# PCIE_CLK.net
KiCad netlist of a schematic drawn in Altium Designer
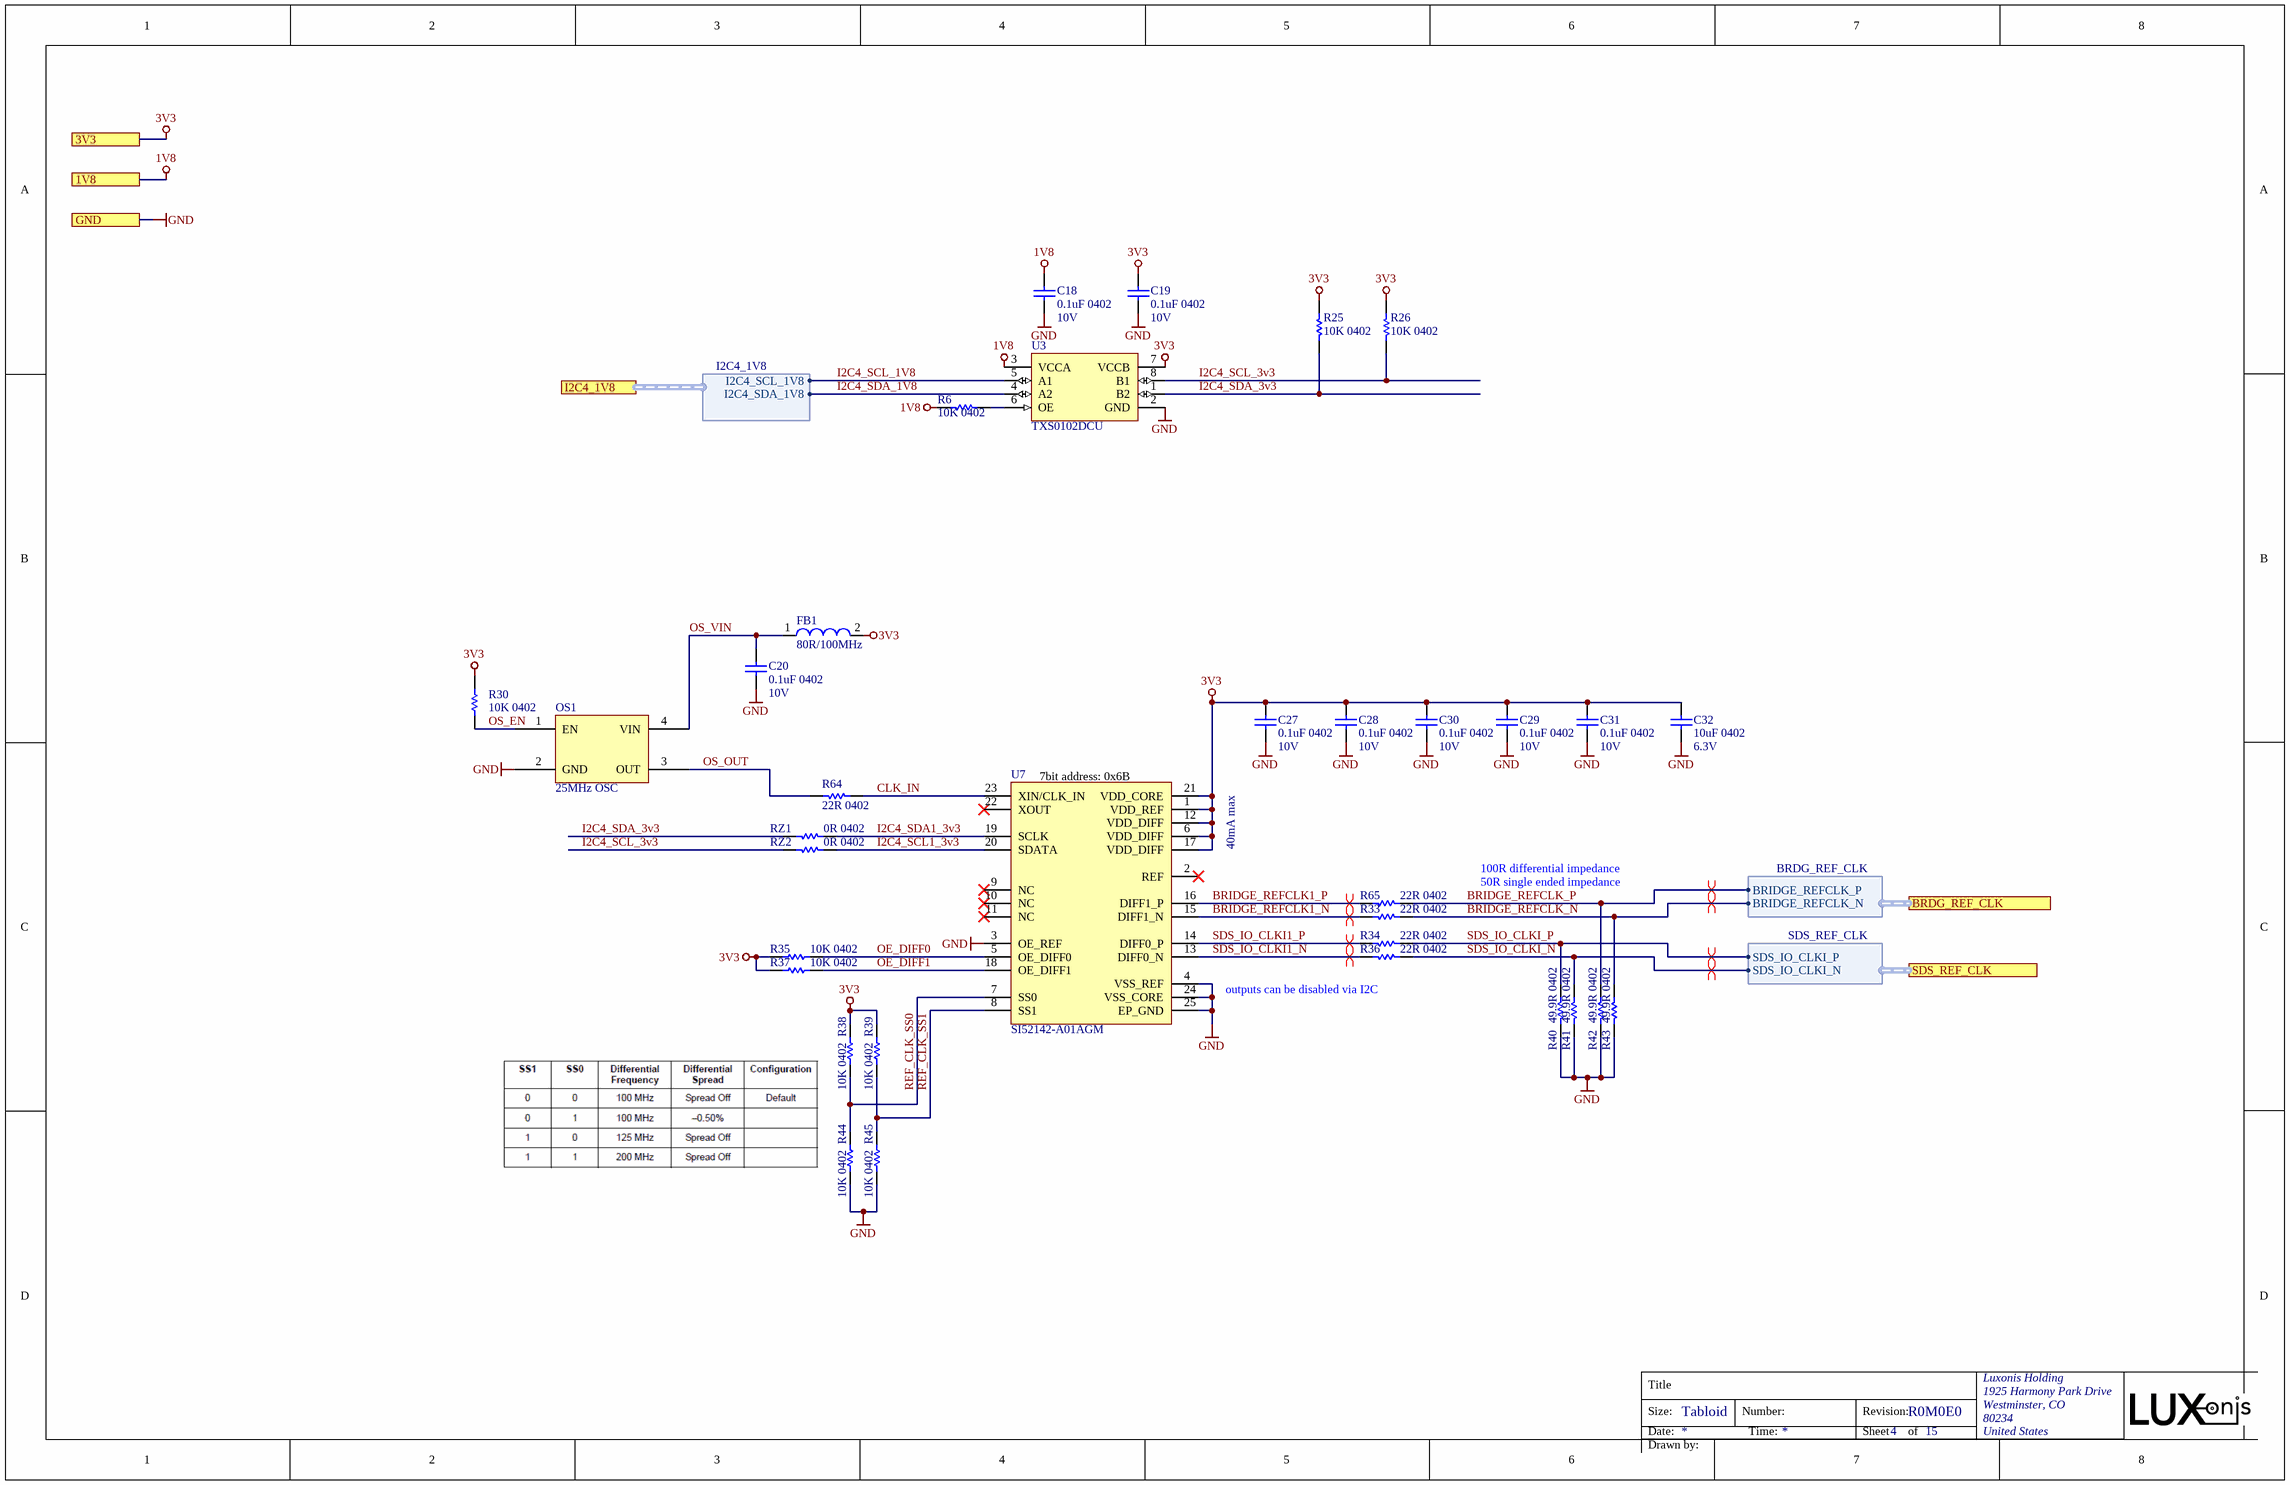
[diagram p0: PCIE_CLK.SchDoc]

(export (version "E")
  (design (tool "Eeschema 10.0.6"))
  (components
    (comp (ref "C18")
      (value "0.1uF 0402")
      (footprint "CAP_Altium_Vault_Generic:CAPC0402(1005)70_N")
      (description "CAP CER 0.1UF 10V X7R 0402 5%")
      (fields (field (name "TOLERANCE") "5%") (field (name "VOLTAGE RATING") "10V"))
      (libsource (lib "LuxonisMaster") (part "GRM155R71A104JA01D"))
    )
    (comp (ref "C19")
      (value "0.1uF 0402")
      (footprint "CAP_Altium_Vault_Generic:CAPC0402(1005)70_N")
      (description "CAP CER 0.1UF 10V X7R 0402 5%")
      (fields (field (name "TOLERANCE") "5%") (field (name "VOLTAGE RATING") "10V"))
      (libsource (lib "LuxonisMaster") (part "GRM155R71A104JA01D"))
    )
    (comp (ref "C20")
      (value "0.1uF 0402")
      (footprint "CAP_Altium_Vault_Generic:CAPC0402(1005)70_N")
      (description "CAP CER 0.1UF 10V X7R 0402 5%")
      (fields (field (name "TOLERANCE") "5%") (field (name "VOLTAGE RATING") "10V"))
      (libsource (lib "LuxonisMaster") (part "GRM155R71A104JA01D"))
    )
    (comp (ref "C27")
      (value "0.1uF 0402")
      (footprint "CAP_Altium_Vault_Generic:CAPC0402(1005)70_N")
      (description "CAP CER 0.1UF 10V X7R 0402 5%")
      (fields (field (name "TOLERANCE") "5%") (field (name "VOLTAGE RATING") "10V"))
      (libsource (lib "LuxonisMaster") (part "GRM155R71A104JA01D"))
    )
    (comp (ref "C28")
      (value "0.1uF 0402")
      (footprint "CAP_Altium_Vault_Generic:CAPC0402(1005)70_N")
      (description "CAP CER 0.1UF 10V X7R 0402 5%")
      (fields (field (name "TOLERANCE") "5%") (field (name "VOLTAGE RATING") "10V"))
      (libsource (lib "LuxonisMaster") (part "GRM155R71A104JA01D"))
    )
    (comp (ref "C29")
      (value "0.1uF 0402")
      (footprint "CAP_Altium_Vault_Generic:CAPC0402(1005)70_N")
      (description "CAP CER 0.1UF 10V X7R 0402 5%")
      (fields (field (name "TOLERANCE") "5%") (field (name "VOLTAGE RATING") "10V"))
      (libsource (lib "LuxonisMaster") (part "GRM155R71A104JA01D"))
    )
    (comp (ref "C30")
      (value "0.1uF 0402")
      (footprint "CAP_Altium_Vault_Generic:CAPC0402(1005)70_N")
      (description "CAP CER 0.1UF 10V X7R 0402 5%")
      (fields (field (name "TOLERANCE") "5%") (field (name "VOLTAGE RATING") "10V"))
      (libsource (lib "LuxonisMaster") (part "GRM155R71A104JA01D"))
    )
    (comp (ref "C31")
      (value "0.1uF 0402")
      (footprint "CAP_Altium_Vault_Generic:CAPC0402(1005)70_N")
      (description "CAP CER 0.1UF 10V X7R 0402 5%")
      (fields (field (name "TOLERANCE") "5%") (field (name "VOLTAGE RATING") "10V"))
      (libsource (lib "LuxonisMaster") (part "GRM155R71A104JA01D"))
    )
    (comp (ref "C32")
      (value "10uF 0402")
      (footprint "CAP_Altium_Vault_Generic:CAPC0402(1005)70_N")
      (description "CAP CER 10UF 6.3V X5R 0402 20%")
      (fields (field (name "TOLERANCE") "20%") (field (name "VOLTAGE RATING") "6.3V"))
      (libsource (lib "LuxonisMaster") (part "GRM155R60J106ME15D"))
    )
    (comp (ref "FB1")
      (value "80R/100MHz")
      (footprint "LuxonisMaster:BK1608HS800-T_N")
      (description "FERRITE BEAD 80 OHM 0603 1LN")
      (fields (field (name "TOLERANCE") "25%"))
      (libsource (lib "LuxonisMaster") (part "BK1608HS800-T"))
    )
    (comp (ref "OS1")
      (value "25MHz OSC")
      (footprint "BW2098POE:ASDMB-25.000MHZ-LC-T")
      (description "MEMS OSC XO 25.0000MHZ LVCMOS")
      (libsource (lib "BW2098POE") (part "ASDMB-25.000MHZ-LC-T"))
    )
    (comp (ref "R6")
      (value "10K 0402")
      (footprint "RESC0402(1005)_N")
      (fields (field (name "TOLERANCE") "1%"))
      (libsource (lib "LuxonisMaster") (part "RC0402FR-1310KL"))
    )
    (comp (ref "R25")
      (value "10K 0402")
      (footprint "RESC0402(1005)_N")
      (fields (field (name "TOLERANCE") "1%"))
      (libsource (lib "LuxonisMaster") (part "RC0402FR-1310KL"))
    )
    (comp (ref "R26")
      (value "10K 0402")
      (footprint "RESC0402(1005)_N")
      (fields (field (name "TOLERANCE") "1%"))
      (libsource (lib "LuxonisMaster") (part "RC0402FR-1310KL"))
    )
    (comp (ref "R30")
      (value "10K 0402")
      (footprint "RESC0402(1005)_N")
      (fields (field (name "TOLERANCE") "1%"))
      (libsource (lib "LuxonisMaster") (part "RC0402FR-1310KL"))
    )
    (comp (ref "R33")
      (value "22R 0402")
      (footprint "RES_Altium_Vault_Generic:RESC0402(1005)_L")
      (description "RES SMD 22 OHM 1% 1/16W 0402")
      (fields (field (name "TOLERANCE") "1%"))
      (libsource (lib "BW2098POE") (part "RC0402FR-0722RL"))
    )
    (comp (ref "R34")
      (value "22R 0402")
      (footprint "RES_Altium_Vault_Generic:RESC0402(1005)_L")
      (description "RES SMD 22 OHM 1% 1/16W 0402")
      (fields (field (name "TOLERANCE") "1%"))
      (libsource (lib "BW2098POE") (part "RC0402FR-0722RL"))
    )
    (comp (ref "R35")
      (value "10K 0402")
      (footprint "RESC0402(1005)_N")
      (fields (field (name "TOLERANCE") "1%"))
      (libsource (lib "LuxonisMaster") (part "RC0402FR-1310KL"))
    )
    (comp (ref "R36")
      (value "22R 0402")
      (footprint "RES_Altium_Vault_Generic:RESC0402(1005)_L")
      (description "RES SMD 22 OHM 1% 1/16W 0402")
      (fields (field (name "TOLERANCE") "1%"))
      (libsource (lib "BW2098POE") (part "RC0402FR-0722RL"))
    )
    (comp (ref "R37")
      (value "10K 0402")
      (footprint "RESC0402(1005)_N")
      (fields (field (name "TOLERANCE") "1%"))
      (libsource (lib "LuxonisMaster") (part "RC0402FR-1310KL"))
    )
    (comp (ref "R38")
      (value "10K 0402")
      (footprint "RESC0402(1005)_N")
      (fields (field (name "TOLERANCE") "1%"))
      (libsource (lib "LuxonisMaster") (part "RC0402FR-1310KL"))
    )
    (comp (ref "R39")
      (value "10K 0402")
      (footprint "RESC0402(1005)_N")
      (fields (field (name "TOLERANCE") "1%"))
      (libsource (lib "LuxonisMaster") (part "RC0402FR-1310KL"))
    )
    (comp (ref "R40")
      (value "49.9R 0402")
      (footprint "RES_Altium_Vault_Generic:RESC0402(1005)_L")
      (description "RES SMD 49.9 OHM 1% 1/16W 0402")
      (fields (field (name "TOLERANCE") "1%"))
      (libsource (lib "LuxonisMaster") (part "RC0402FR-0749R9L"))
    )
    (comp (ref "R41")
      (value "49.9R 0402")
      (footprint "RES_Altium_Vault_Generic:RESC0402(1005)_L")
      (description "RES SMD 49.9 OHM 1% 1/16W 0402")
      (fields (field (name "TOLERANCE") "1%"))
      (libsource (lib "LuxonisMaster") (part "RC0402FR-0749R9L"))
    )
    (comp (ref "R42")
      (value "49.9R 0402")
      (footprint "RES_Altium_Vault_Generic:RESC0402(1005)_L")
      (description "RES SMD 49.9 OHM 1% 1/16W 0402")
      (fields (field (name "TOLERANCE") "1%"))
      (libsource (lib "LuxonisMaster") (part "RC0402FR-0749R9L"))
    )
    (comp (ref "R43")
      (value "49.9R 0402")
      (footprint "RES_Altium_Vault_Generic:RESC0402(1005)_L")
      (description "RES SMD 49.9 OHM 1% 1/16W 0402")
      (fields (field (name "TOLERANCE") "1%"))
      (libsource (lib "LuxonisMaster") (part "RC0402FR-0749R9L"))
    )
    (comp (ref "R44")
      (value "10K 0402")
      (footprint "RESC0402(1005)_N")
      (fields (field (name "TOLERANCE") "1%"))
      (libsource (lib "LuxonisMaster") (part "RC0402FR-1310KL"))
    )
    (comp (ref "R45")
      (value "10K 0402")
      (footprint "RESC0402(1005)_N")
      (fields (field (name "TOLERANCE") "1%"))
      (libsource (lib "LuxonisMaster") (part "RC0402FR-1310KL"))
    )
    (comp (ref "R64")
      (value "22R 0402")
      (footprint "RESC0402(1005)_N")
      (description "RES SMD 22 OHM 1% 1/16W 0402")
      (fields (field (name "TOLERANCE") "1%"))
      (libsource (lib "BW2098POE") (part "RC0402FR-0722RL"))
    )
    (comp (ref "R65")
      (value "22R 0402")
      (footprint "RES_Altium_Vault_Generic:RESC0402(1005)_L")
      (description "RES SMD 22 OHM 1% 1/16W 0402")
      (fields (field (name "TOLERANCE") "1%"))
      (libsource (lib "BW2098POE") (part "RC0402FR-0722RL"))
    )
    (comp (ref "RZ1")
      (value "0R 0402")
      (footprint "RESC0402(1005)_N")
      (description "RES SMD 0 OHM JUMPER 1/16W 0402")
      (fields (field (name "TOLERANCE") "5%"))
      (libsource (lib "LuxonisMaster") (part "CRCW04020000Z0ED"))
    )
    (comp (ref "RZ2")
      (value "0R 0402")
      (footprint "RESC0402(1005)_N")
      (description "RES SMD 0 OHM JUMPER 1/16W 0402")
      (fields (field (name "TOLERANCE") "5%"))
      (libsource (lib "LuxonisMaster") (part "CRCW04020000Z0ED"))
    )
    (comp (ref "U3")
      (value "TXS0102DCU")
      (footprint "BW2098POE:TXS0102DCUR")
      (description "TEXAS INSTRUMENTS - TXS0102DCUR - IC, TRANSLATOR, 2 BIT, BI, US-8")
      (libsource (lib "BW2098POE") (part "TXS0102DCUR"))
    )
    (comp (ref "U7")
      (value "SI52142-A01AGM")
      (footprint "BW2098POE:SI52142-A01AGM")
      (description "IC CLK GENERATOR 200MHZ 24QFN")
      (libsource (lib "BW2098POE") (part "SI52142-A01AGM"))
    )
  )
  (nets
    (net (code "4") (name "/BRIDGE_REFCLK1_N") (class "Default")
      (node (ref "R33") (pin "2") (pinfunction "2_2") (pintype "passive"))
      (node (ref "U7") (pin "15") (pinfunction "DIFF1_N_15") (pintype "passive"))
    )
    (net (code "5") (name "/BRIDGE_REFCLK1_P") (class "Default")
      (node (ref "R65") (pin "2") (pinfunction "2_2") (pintype "passive"))
      (node (ref "U7") (pin "16") (pinfunction "DIFF1_P_16") (pintype "passive"))
    )
    (net (code "6") (name "/BRIDGE_REFCLK_N") (class "Default")
      (node (ref "R33") (pin "1") (pinfunction "1_1") (pintype "passive"))
      (node (ref "R43") (pin "2") (pinfunction "2_2") (pintype "passive"))
    )
    (net (code "7") (name "/BRIDGE_REFCLK_P") (class "Default")
      (node (ref "R42") (pin "2") (pinfunction "2_2") (pintype "passive"))
      (node (ref "R65") (pin "1") (pinfunction "1_1") (pintype "passive"))
    )
    (net (code "8") (name "/CLK_IN") (class "Default")
      (node (ref "R64") (pin "1") (pinfunction "1_1") (pintype "passive"))
      (node (ref "U7") (pin "23") (pinfunction "XIN/CLK_IN_23") (pintype "passive"))
    )
    (net (code "9") (name "/I2C4_SCL1_3v3") (class "Default")
      (node (ref "RZ2") (pin "2") (pinfunction "2_2") (pintype "passive"))
      (node (ref "U7") (pin "20") (pinfunction "SDATA_20") (pintype "passive"))
    )
    (net (code "10") (name "/I2C4_SCL_1V8") (class "Default")
      (node (ref "U3") (pin "5") (pinfunction "A1_5") (pintype "bidirectional"))
    )
    (net (code "11") (name "/I2C4_SCL_3v3") (class "Default")
      (node (ref "R26") (pin "2") (pinfunction "2_2") (pintype "passive"))
      (node (ref "RZ2") (pin "1") (pinfunction "1_1") (pintype "passive"))
      (node (ref "U3") (pin "8") (pinfunction "B1_8") (pintype "bidirectional"))
    )
    (net (code "12") (name "/I2C4_SDA1_3v3") (class "Default")
      (node (ref "RZ1") (pin "2") (pinfunction "2_2") (pintype "passive"))
      (node (ref "U7") (pin "19") (pinfunction "SCLK_19") (pintype "passive"))
    )
    (net (code "13") (name "/I2C4_SDA_1V8") (class "Default")
      (node (ref "U3") (pin "4") (pinfunction "A2_4") (pintype "bidirectional"))
    )
    (net (code "14") (name "/I2C4_SDA_3v3") (class "Default")
      (node (ref "R25") (pin "2") (pinfunction "2_2") (pintype "passive"))
      (node (ref "RZ1") (pin "1") (pinfunction "1_1") (pintype "passive"))
      (node (ref "U3") (pin "1") (pinfunction "B2_1") (pintype "bidirectional"))
    )
    (net (code "15") (name "/OE_DIFF0") (class "Default")
      (node (ref "R35") (pin "2") (pinfunction "2_2") (pintype "passive"))
      (node (ref "U7") (pin "5") (pinfunction "OE_DIFF0_5") (pintype "passive"))
    )
    (net (code "16") (name "/OE_DIFF1") (class "Default")
      (node (ref "R37") (pin "2") (pinfunction "2_2") (pintype "passive"))
      (node (ref "U7") (pin "18") (pinfunction "OE_DIFF1_18") (pintype "passive"))
    )
    (net (code "17") (name "/OS_EN") (class "Default")
      (node (ref "OS1") (pin "1") (pinfunction "EN_1") (pintype "passive"))
      (node (ref "R30") (pin "1") (pinfunction "1_1") (pintype "passive"))
    )
    (net (code "18") (name "/OS_OUT") (class "Default")
      (node (ref "OS1") (pin "3") (pinfunction "OUT_3") (pintype "passive"))
      (node (ref "R64") (pin "2") (pinfunction "2_2") (pintype "passive"))
    )
    (net (code "19") (name "/OS_VIN") (class "Default")
      (node (ref "C20") (pin "1") (pinfunction "1_1") (pintype "passive"))
      (node (ref "FB1") (pin "1") (pinfunction "1_1") (pintype "passive"))
      (node (ref "OS1") (pin "4") (pinfunction "VIN_4") (pintype "passive"))
    )
    (net (code "20") (name "/REF_CLK_SS0") (class "Default")
      (node (ref "R38") (pin "2") (pinfunction "2_2") (pintype "passive"))
      (node (ref "R44") (pin "1") (pinfunction "1_1") (pintype "passive"))
      (node (ref "U7") (pin "7") (pinfunction "SS0_7") (pintype "passive"))
    )
    (net (code "21") (name "/REF_CLK_SS1") (class "Default")
      (node (ref "R39") (pin "2") (pinfunction "2_2") (pintype "passive"))
      (node (ref "R45") (pin "1") (pinfunction "1_1") (pintype "passive"))
      (node (ref "U7") (pin "8") (pinfunction "SS1_8") (pintype "passive"))
    )
    (net (code "22") (name "/SDS_IO_CLKI1_N") (class "Default")
      (node (ref "R36") (pin "2") (pinfunction "2_2") (pintype "passive"))
      (node (ref "U7") (pin "13") (pinfunction "DIFF0_N_13") (pintype "passive"))
    )
    (net (code "23") (name "/SDS_IO_CLKI1_P") (class "Default")
      (node (ref "R34") (pin "2") (pinfunction "2_2") (pintype "passive"))
      (node (ref "U7") (pin "14") (pinfunction "DIFF0_P_14") (pintype "passive"))
    )
    (net (code "24") (name "/SDS_IO_CLKI_N") (class "Default")
      (node (ref "R36") (pin "1") (pinfunction "1_1") (pintype "passive"))
      (node (ref "R41") (pin "2") (pinfunction "2_2") (pintype "passive"))
    )
    (net (code "25") (name "/SDS_IO_CLKI_P") (class "Default")
      (node (ref "R34") (pin "1") (pinfunction "1_1") (pintype "passive"))
      (node (ref "R40") (pin "1") (pinfunction "1_1") (pintype "passive"))
    )
    (net (code "29") (name "1V8") (class "Default")
      (node (ref "C18") (pin "2") (pinfunction "2_2") (pintype "passive"))
      (node (ref "R6") (pin "2") (pinfunction "2_2") (pintype "passive"))
      (node (ref "U3") (pin "3") (pinfunction "VCCA_3") (pintype "power_in"))
    )
    (net (code "30") (name "3V3") (class "Default")
      (node (ref "C19") (pin "2") (pinfunction "2_2") (pintype "passive"))
      (node (ref "C27") (pin "1") (pinfunction "1_1") (pintype "passive"))
      (node (ref "C28") (pin "1") (pinfunction "1_1") (pintype "passive"))
      (node (ref "C29") (pin "1") (pinfunction "1_1") (pintype "passive"))
      (node (ref "C30") (pin "1") (pinfunction "1_1") (pintype "passive"))
      (node (ref "C31") (pin "1") (pinfunction "1_1") (pintype "passive"))
      (node (ref "C32") (pin "2") (pinfunction "2_2") (pintype "passive"))
      (node (ref "FB1") (pin "2") (pinfunction "2_2") (pintype "passive"))
      (node (ref "R25") (pin "1") (pinfunction "1_1") (pintype "passive"))
      (node (ref "R26") (pin "1") (pinfunction "1_1") (pintype "passive"))
      (node (ref "R30") (pin "2") (pinfunction "2_2") (pintype "passive"))
      (node (ref "R35") (pin "1") (pinfunction "1_1") (pintype "passive"))
      (node (ref "R37") (pin "1") (pinfunction "1_1") (pintype "passive"))
      (node (ref "R38") (pin "1") (pinfunction "1_1") (pintype "passive"))
      (node (ref "R39") (pin "1") (pinfunction "1_1") (pintype "passive"))
      (node (ref "U3") (pin "7") (pinfunction "VCCB_7") (pintype "power_in"))
      (node (ref "U7") (pin "1") (pinfunction "VDD_REF_1") (pintype "passive"))
      (node (ref "U7") (pin "12") (pinfunction "VDD_DIFF_12") (pintype "passive"))
      (node (ref "U7") (pin "17") (pinfunction "VDD_DIFF_17") (pintype "passive"))
      (node (ref "U7") (pin "21") (pinfunction "VDD_CORE_21") (pintype "passive"))
      (node (ref "U7") (pin "6") (pinfunction "VDD_DIFF_6") (pintype "passive"))
    )
    (net (code "31") (name "GND") (class "Default")
      (node (ref "C18") (pin "1") (pinfunction "1_1") (pintype "passive"))
      (node (ref "C19") (pin "1") (pinfunction "1_1") (pintype "passive"))
      (node (ref "C20") (pin "2") (pinfunction "2_2") (pintype "passive"))
      (node (ref "C27") (pin "2") (pinfunction "2_2") (pintype "passive"))
      (node (ref "C28") (pin "2") (pinfunction "2_2") (pintype "passive"))
      (node (ref "C29") (pin "2") (pinfunction "2_2") (pintype "passive"))
      (node (ref "C30") (pin "2") (pinfunction "2_2") (pintype "passive"))
      (node (ref "C31") (pin "2") (pinfunction "2_2") (pintype "passive"))
      (node (ref "C32") (pin "1") (pinfunction "1_1") (pintype "passive"))
      (node (ref "OS1") (pin "2") (pinfunction "GND_2") (pintype "passive"))
      (node (ref "R40") (pin "2") (pinfunction "2_2") (pintype "passive"))
      (node (ref "R41") (pin "1") (pinfunction "1_1") (pintype "passive"))
      (node (ref "R42") (pin "1") (pinfunction "1_1") (pintype "passive"))
      (node (ref "R43") (pin "1") (pinfunction "1_1") (pintype "passive"))
      (node (ref "R44") (pin "2") (pinfunction "2_2") (pintype "passive"))
      (node (ref "R45") (pin "2") (pinfunction "2_2") (pintype "passive"))
      (node (ref "U3") (pin "2") (pinfunction "GND_2") (pintype "power_in"))
      (node (ref "U7") (pin "24") (pinfunction "VSS_CORE_24") (pintype "passive"))
      (node (ref "U7") (pin "25") (pinfunction "EP_GND_25") (pintype "passive"))
      (node (ref "U7") (pin "3") (pinfunction "OE_REF_3") (pintype "passive"))
      (node (ref "U7") (pin "4") (pinfunction "VSS_REF_4") (pintype "passive"))
    )
    (net (code "32") (name "Net-(U3-OE)") (class "Default")
      (node (ref "R6") (pin "1") (pinfunction "1_1") (pintype "passive"))
      (node (ref "U3") (pin "6") (pinfunction "OE_6") (pintype "input"))
    )
    (net (code "33") (name "unconnected-(U7-NC-Pad9)") (class "Default")
      (node (ref "U7") (pin "9") (pinfunction "NC_9") (pintype "passive+no_connect"))
    )
    (net (code "34") (name "unconnected-(U7-NC-Pad10)") (class "Default")
      (node (ref "U7") (pin "10") (pinfunction "NC_10") (pintype "passive+no_connect"))
    )
    (net (code "35") (name "unconnected-(U7-NC-Pad11)") (class "Default")
      (node (ref "U7") (pin "11") (pinfunction "NC_11") (pintype "passive+no_connect"))
    )
    (net (code "36") (name "unconnected-(U7-REF-Pad2)") (class "Default")
      (node (ref "U7") (pin "2") (pinfunction "REF_2") (pintype "passive+no_connect"))
    )
    (net (code "37") (name "unconnected-(U7-XOUT-Pad22)") (class "Default")
      (node (ref "U7") (pin "22") (pinfunction "XOUT_22") (pintype "passive+no_connect"))
    )
  )
)
